# 2_-_POWER.net
KiCad netlist of a schematic drawn in Altium Designer
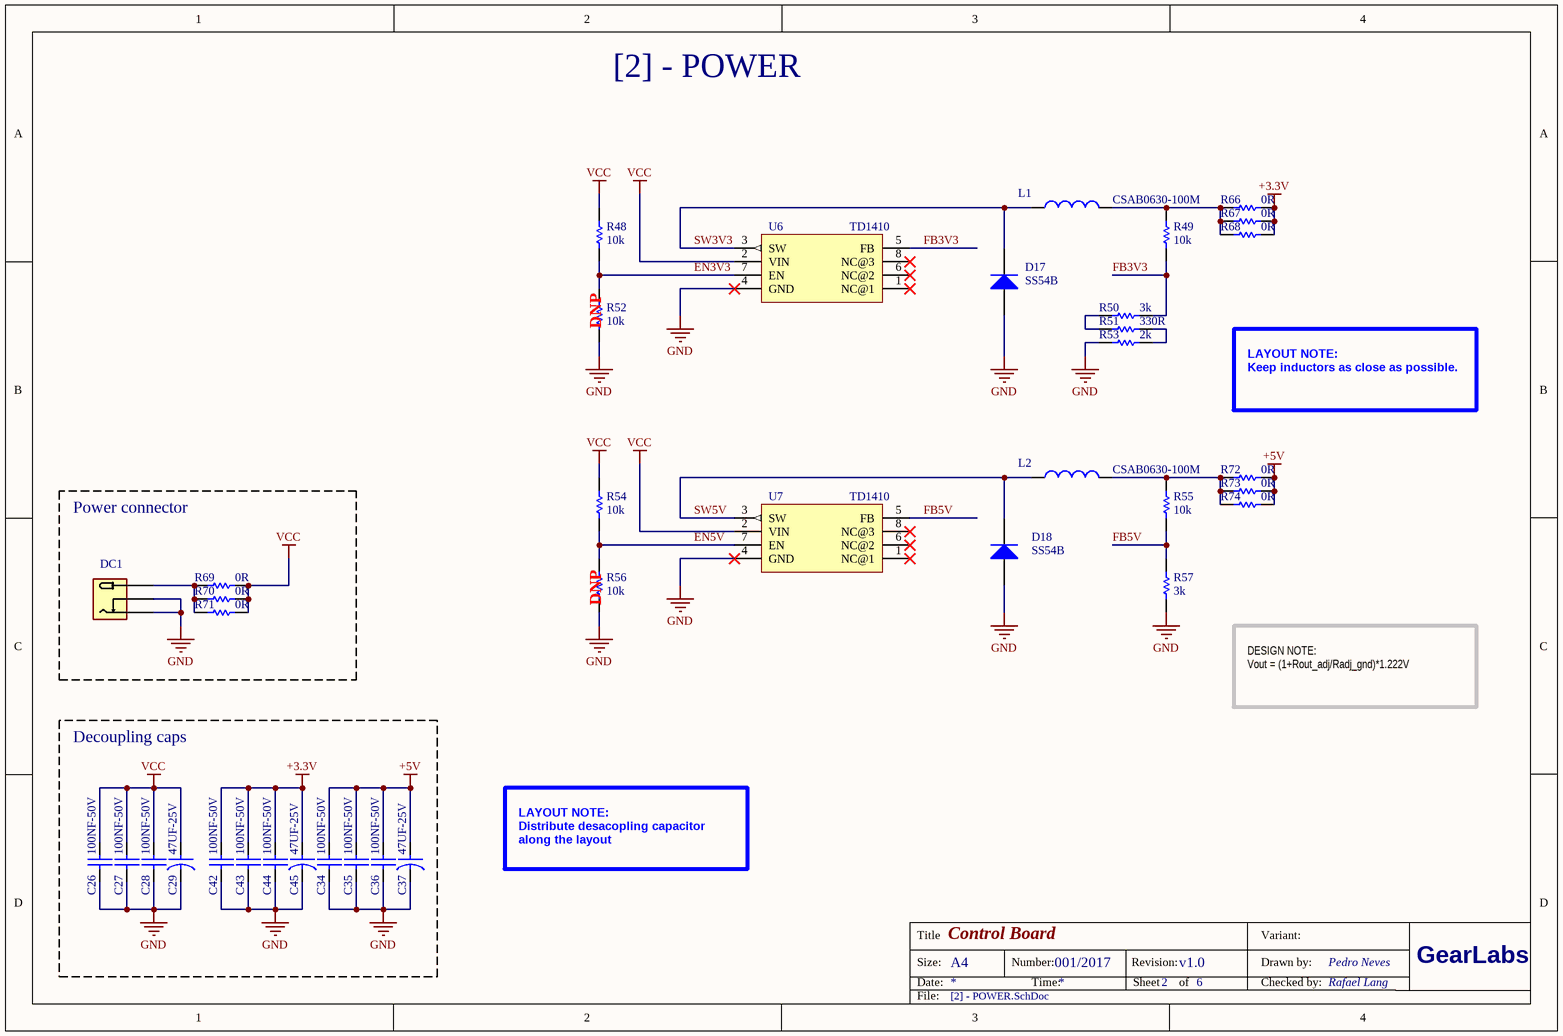
[diagram p0: [2] - POWER.SchDoc]

(export (version "E")
  (design (tool "Eeschema 10.0.6"))
  (components
    (comp (ref "C26")
      (value "100NF-50V")
      (footprint "C0603")
      (fields (field (name "MPN") "CC0603KRX7R9BB104") (field (name "Comment") "302010138"))
      (libsource (lib "Seeed-Capacitor") (part "CERAMIC-100NF-50V-10%-X7R(0603)"))
    )
    (comp (ref "C27")
      (value "100NF-50V")
      (footprint "C0603")
      (fields (field (name "MPN") "CC0603KRX7R9BB104") (field (name "Comment") "302010138"))
      (libsource (lib "Seeed-Capacitor") (part "CERAMIC-100NF-50V-10%-X7R(0603)"))
    )
    (comp (ref "C28")
      (value "100NF-50V")
      (footprint "C0603")
      (fields (field (name "MPN") "CC0603KRX7R9BB104") (field (name "Comment") "302010138"))
      (libsource (lib "Seeed-Capacitor") (part "CERAMIC-100NF-50V-10%-X7R(0603)"))
    )
    (comp (ref "C29")
      (value "47UF-25V")
      (footprint "ELECTRO-SMD-C-6MM")
      (fields (field (name "MPN") "CS1E470M-CRE54") (field (name "Comment") "302030059"))
      (libsource (lib "Seeed-Capacitor") (part "ALUMINUM-SMD-47UF-25V(D6.3-H5.3MM)"))
    )
    (comp (ref "C34")
      (value "100NF-50V")
      (footprint "C0603")
      (fields (field (name "MPN") "CC0603KRX7R9BB104") (field (name "Comment") "302010138"))
      (libsource (lib "Seeed-Capacitor") (part "CERAMIC-100NF-50V-10%-X7R(0603)"))
    )
    (comp (ref "C35")
      (value "100NF-50V")
      (footprint "C0603")
      (fields (field (name "MPN") "CC0603KRX7R9BB104") (field (name "Comment") "302010138"))
      (libsource (lib "Seeed-Capacitor") (part "CERAMIC-100NF-50V-10%-X7R(0603)"))
    )
    (comp (ref "C36")
      (value "100NF-50V")
      (footprint "C0603")
      (fields (field (name "MPN") "CC0603KRX7R9BB104") (field (name "Comment") "302010138"))
      (libsource (lib "Seeed-Capacitor") (part "CERAMIC-100NF-50V-10%-X7R(0603)"))
    )
    (comp (ref "C37")
      (value "47UF-25V")
      (footprint "ELECTRO-SMD-C-6MM")
      (fields (field (name "MPN") "CS1E470M-CRE54") (field (name "Comment") "302030059"))
      (libsource (lib "Seeed-Capacitor") (part "ALUMINUM-SMD-47UF-25V(D6.3-H5.3MM)"))
    )
    (comp (ref "C42")
      (value "100NF-50V")
      (footprint "C0603")
      (fields (field (name "MPN") "CC0603KRX7R9BB104") (field (name "Comment") "302010138"))
      (libsource (lib "Seeed-Capacitor") (part "CERAMIC-100NF-50V-10%-X7R(0603)"))
    )
    (comp (ref "C43")
      (value "100NF-50V")
      (footprint "C0603")
      (fields (field (name "MPN") "CC0603KRX7R9BB104") (field (name "Comment") "302010138"))
      (libsource (lib "Seeed-Capacitor") (part "CERAMIC-100NF-50V-10%-X7R(0603)"))
    )
    (comp (ref "C44")
      (value "100NF-50V")
      (footprint "C0603")
      (fields (field (name "MPN") "CC0603KRX7R9BB104") (field (name "Comment") "302010138"))
      (libsource (lib "Seeed-Capacitor") (part "CERAMIC-100NF-50V-10%-X7R(0603)"))
    )
    (comp (ref "C45")
      (value "47UF-25V")
      (footprint "ELECTRO-SMD-C-6MM")
      (fields (field (name "MPN") "CS1E470M-CRE54") (field (name "Comment") "302030059"))
      (libsource (lib "Seeed-Capacitor") (part "ALUMINUM-SMD-47UF-25V(D6.3-H5.3MM)"))
    )
    (comp (ref "D17")
      (value "304020021")
      (footprint "DO-214AA")
      (fields (field (name "MPN") "SS54B"))
      (libsource (lib "Seeed-Diode") (part "SMD-DIODE-SCHOTTKY-28V-5A(DO-214AA)"))
    )
    (comp (ref "D18")
      (value "304020021")
      (footprint "DO-214AA")
      (fields (field (name "MPN") "SS54B"))
      (libsource (lib "Seeed-Diode") (part "SMD-DIODE-SCHOTTKY-28V-5A(DO-214AA)"))
    )
    (comp (ref "DC1")
      (value "320120003")
      (footprint "3P-L14.2*W11.0*H9.0MM")
      (libsource (lib "Seeed-Connector") (part "JACK-DC-005'DC-005'"))
    )
    (comp (ref "L1")
      (value "303010016")
      (footprint "SMD-2P-L6.0XW6.0XH3.0MM")
      (fields (field (name "MPN") "CSAB0630-100M"))
      (libsource (lib "Seeed-Inductor") (part "SMD-INDUCTOR-10UH-20%(2P-6X6MM)'0630'"))
    )
    (comp (ref "L2")
      (value "303010016")
      (footprint "SMD-2P-L6.0XW6.0XH3.0MM")
      (fields (field (name "MPN") "CSAB0630-100M"))
      (libsource (lib "Seeed-Inductor") (part "SMD-INDUCTOR-10UH-20%(2P-6X6MM)'0630'"))
    )
    (comp (ref "R48")
      (value "10k")
      (footprint "R0603")
      (fields (field (name "MPN") "RC0603JR-0710KL") (field (name "Comment") "301010293"))
      (libsource (lib "Seeed-Resistor") (part "SMD-RES-10K-5%-1/10W(0603)"))
    )
    (comp (ref "R49")
      (value "10k")
      (footprint "R0603")
      (fields (field (name "MPN") "RC0603FR-0710KL") (field (name "Comment") "301010299"))
      (libsource (lib "Seeed-Resistor") (part "SMD-RES-10K-1%-1/10W(0603)"))
    )
    (comp (ref "R50")
      (value "3k")
      (footprint "R0603")
      (fields (field (name "MPN") "RC0603FR-073KL") (field (name "Comment") "301010170"))
      (libsource (lib "Seeed-Resistor") (part "SMD-RES-3K-1%-1/10W(0603)"))
    )
    (comp (ref "R51")
      (value "330R")
      (footprint "R0603")
      (fields (field (name "MPN") "RC0603FR-07330RL") (field (name "Comment") "301010300"))
      (libsource (lib "Seeed-Resistor") (part "SMD-RES-330R-1%-1/10W(0603)"))
    )
    (comp (ref "R52")
      (value "10k")
      (footprint "R0603")
      (fields (field (name "MPN") "RC0603JR-0710KL") (field (name "Comment") "301010293"))
      (libsource (lib "Seeed-Resistor") (part "SMD-RES-10K-5%-1/10W(0603)"))
    )
    (comp (ref "R53")
      (value "2k")
      (footprint "R0603")
      (fields (field (name "MPN") "RC0603FR-072KL") (field (name "Comment") "301010221"))
      (libsource (lib "Seeed-Resistor") (part "SMD-RES-2K-1%-1/10W(0603)"))
    )
    (comp (ref "R54")
      (value "10k")
      (footprint "R0603")
      (fields (field (name "MPN") "RC0603JR-0710KL") (field (name "Comment") "301010293"))
      (libsource (lib "Seeed-Resistor") (part "SMD-RES-10K-5%-1/10W(0603)"))
    )
    (comp (ref "R55")
      (value "10k")
      (footprint "R0603")
      (fields (field (name "MPN") "RC0603FR-0710KL") (field (name "Comment") "301010299"))
      (libsource (lib "Seeed-Resistor") (part "SMD-RES-10K-1%-1/10W(0603)"))
    )
    (comp (ref "R56")
      (value "10k")
      (footprint "R0603")
      (fields (field (name "MPN") "RC0603JR-0710KL") (field (name "Comment") "301010293"))
      (libsource (lib "Seeed-Resistor") (part "SMD-RES-10K-5%-1/10W(0603)"))
    )
    (comp (ref "R57")
      (value "3k")
      (footprint "R0603")
      (fields (field (name "MPN") "RC0603FR-073KL") (field (name "Comment") "301010170"))
      (libsource (lib "Seeed-Resistor") (part "SMD-RES-3K-1%-1/10W(0603)"))
    )
    (comp (ref "R66")
      (value "0R")
      (footprint "R0603")
      (fields (field (name "MPN") "RC0603JR-070RL") (field (name "Comment") "301010292"))
      (libsource (lib "Seeed-Resistor") (part "SMD-RES-0R-5%-1/10W(0603)"))
    )
    (comp (ref "R67")
      (value "0R")
      (footprint "R0603")
      (fields (field (name "MPN") "RC0603JR-070RL") (field (name "Comment") "301010292"))
      (libsource (lib "Seeed-Resistor") (part "SMD-RES-0R-5%-1/10W(0603)"))
    )
    (comp (ref "R68")
      (value "0R")
      (footprint "R0603")
      (fields (field (name "MPN") "RC0603JR-070RL") (field (name "Comment") "301010292"))
      (libsource (lib "Seeed-Resistor") (part "SMD-RES-0R-5%-1/10W(0603)"))
    )
    (comp (ref "R69")
      (value "0R")
      (footprint "R0603")
      (fields (field (name "MPN") "RC0603JR-070RL") (field (name "Comment") "301010292"))
      (libsource (lib "Seeed-Resistor") (part "SMD-RES-0R-5%-1/10W(0603)"))
    )
    (comp (ref "R70")
      (value "0R")
      (footprint "R0603")
      (fields (field (name "MPN") "RC0603JR-070RL") (field (name "Comment") "301010292"))
      (libsource (lib "Seeed-Resistor") (part "SMD-RES-0R-5%-1/10W(0603)"))
    )
    (comp (ref "R71")
      (value "0R")
      (footprint "R0603")
      (fields (field (name "MPN") "RC0603JR-070RL") (field (name "Comment") "301010292"))
      (libsource (lib "Seeed-Resistor") (part "SMD-RES-0R-5%-1/10W(0603)"))
    )
    (comp (ref "R72")
      (value "0R")
      (footprint "R0603")
      (fields (field (name "MPN") "RC0603JR-070RL") (field (name "Comment") "301010292"))
      (libsource (lib "Seeed-Resistor") (part "SMD-RES-0R-5%-1/10W(0603)"))
    )
    (comp (ref "R73")
      (value "0R")
      (footprint "R0603")
      (fields (field (name "MPN") "RC0603JR-070RL") (field (name "Comment") "301010292"))
      (libsource (lib "Seeed-Resistor") (part "SMD-RES-0R-5%-1/10W(0603)"))
    )
    (comp (ref "R74")
      (value "0R")
      (footprint "R0603")
      (fields (field (name "MPN") "RC0603JR-070RL") (field (name "Comment") "301010292"))
      (libsource (lib "Seeed-Resistor") (part "SMD-RES-0R-5%-1/10W(0603)"))
    )
    (comp (ref "U6")
      (value "TD1410")
      (footprint "SOIC8-1.27-5X4MM")
      (libsource (lib "Seeed-IC") (part "PMIC-TD1410(SOIC8)"))
    )
    (comp (ref "U7")
      (value "TD1410")
      (footprint "SOIC8-1.27-5X4MM")
      (libsource (lib "Seeed-IC") (part "PMIC-TD1410(SOIC8)"))
    )
  )
  (nets
    (net (code "1") (name "+3.3V") (class "Default")
      (node (ref "C42") (pin "1") (pinfunction "1_1") (pintype "passive"))
      (node (ref "C43") (pin "1") (pinfunction "1_1") (pintype "passive"))
      (node (ref "C44") (pin "1") (pinfunction "1_1") (pintype "passive"))
      (node (ref "C45") (pin "+") (pinfunction "+_+") (pintype "passive"))
      (node (ref "R66") (pin "2") (pinfunction "2_2") (pintype "passive"))
      (node (ref "R67") (pin "2") (pinfunction "2_2") (pintype "passive"))
      (node (ref "R68") (pin "2") (pinfunction "2_2") (pintype "passive"))
    )
    (net (code "2") (name "+5V") (class "Default")
      (node (ref "C34") (pin "1") (pinfunction "1_1") (pintype "passive"))
      (node (ref "C35") (pin "1") (pinfunction "1_1") (pintype "passive"))
      (node (ref "C36") (pin "1") (pinfunction "1_1") (pintype "passive"))
      (node (ref "C37") (pin "+") (pinfunction "+_+") (pintype "passive"))
      (node (ref "R72") (pin "2") (pinfunction "2_2") (pintype "passive"))
      (node (ref "R73") (pin "2") (pinfunction "2_2") (pintype "passive"))
      (node (ref "R74") (pin "2") (pinfunction "2_2") (pintype "passive"))
    )
    (net (code "3") (name "/EN3V3") (class "Default")
      (node (ref "R48") (pin "1") (pinfunction "1_1") (pintype "passive"))
      (node (ref "R52") (pin "2") (pinfunction "2_2") (pintype "passive"))
      (node (ref "U6") (pin "7") (pinfunction "EN_7") (pintype "passive"))
    )
    (net (code "4") (name "/EN5V") (class "Default")
      (node (ref "R54") (pin "1") (pinfunction "1_1") (pintype "passive"))
      (node (ref "R56") (pin "2") (pinfunction "2_2") (pintype "passive"))
      (node (ref "U7") (pin "7") (pinfunction "EN_7") (pintype "passive"))
    )
    (net (code "5") (name "/FB3V3") (class "Default")
      (node (ref "R49") (pin "1") (pinfunction "1_1") (pintype "passive"))
      (node (ref "R50") (pin "2") (pinfunction "2_2") (pintype "passive"))
      (node (ref "U6") (pin "5") (pinfunction "FB_5") (pintype "passive"))
    )
    (net (code "6") (name "/FB5V") (class "Default")
      (node (ref "R55") (pin "1") (pinfunction "1_1") (pintype "passive"))
      (node (ref "R57") (pin "2") (pinfunction "2_2") (pintype "passive"))
      (node (ref "U7") (pin "5") (pinfunction "FB_5") (pintype "passive"))
    )
    (net (code "7") (name "/SW3V3") (class "Default")
      (node (ref "D17") (pin "-") (pinfunction "-_-") (pintype "passive"))
      (node (ref "L1") (pin "1") (pinfunction "1_1") (pintype "passive"))
      (node (ref "U6") (pin "3") (pinfunction "SW_3") (pintype "output"))
    )
    (net (code "8") (name "/SW5V") (class "Default")
      (node (ref "D18") (pin "-") (pinfunction "-_-") (pintype "passive"))
      (node (ref "L2") (pin "1") (pinfunction "1_1") (pintype "passive"))
      (node (ref "U7") (pin "3") (pinfunction "SW_3") (pintype "output"))
    )
    (net (code "9") (name "GND") (class "Default")
      (node (ref "C26") (pin "2") (pinfunction "2_2") (pintype "passive"))
      (node (ref "C27") (pin "2") (pinfunction "2_2") (pintype "passive"))
      (node (ref "C28") (pin "2") (pinfunction "2_2") (pintype "passive"))
      (node (ref "C29") (pin "-") (pinfunction "-_-") (pintype "passive"))
      (node (ref "C34") (pin "2") (pinfunction "2_2") (pintype "passive"))
      (node (ref "C35") (pin "2") (pinfunction "2_2") (pintype "passive"))
      (node (ref "C36") (pin "2") (pinfunction "2_2") (pintype "passive"))
      (node (ref "C37") (pin "-") (pinfunction "-_-") (pintype "passive"))
      (node (ref "C42") (pin "2") (pinfunction "2_2") (pintype "passive"))
      (node (ref "C43") (pin "2") (pinfunction "2_2") (pintype "passive"))
      (node (ref "C44") (pin "2") (pinfunction "2_2") (pintype "passive"))
      (node (ref "C45") (pin "-") (pinfunction "-_-") (pintype "passive"))
      (node (ref "D17") (pin "+") (pinfunction "+_+") (pintype "passive"))
      (node (ref "D18") (pin "+") (pinfunction "+_+") (pintype "passive"))
      (node (ref "DC1") (pin "-1") (pinfunction "-_-1") (pintype "passive"))
      (node (ref "DC1") (pin "-2") (pinfunction "CDN_-2") (pintype "passive"))
      (node (ref "R52") (pin "1") (pinfunction "1_1") (pintype "passive"))
      (node (ref "R53") (pin "2") (pinfunction "2_2") (pintype "passive"))
      (node (ref "R56") (pin "1") (pinfunction "1_1") (pintype "passive"))
      (node (ref "R57") (pin "1") (pinfunction "1_1") (pintype "passive"))
      (node (ref "U6") (pin "4") (pinfunction "GND_4") (pintype "open_emitter"))
      (node (ref "U7") (pin "4") (pinfunction "GND_4") (pintype "open_emitter"))
    )
    (net (code "10") (name "Net-(DC1-Pad+)") (class "Default")
      (node (ref "DC1") (pin "+") (pinfunction "+_+") (pintype "passive"))
      (node (ref "R69") (pin "1") (pinfunction "1_1") (pintype "passive"))
      (node (ref "R70") (pin "1") (pinfunction "1_1") (pintype "passive"))
      (node (ref "R71") (pin "1") (pinfunction "1_1") (pintype "passive"))
    )
    (net (code "11") (name "Net-(L1-Pad2)") (class "Default")
      (node (ref "L1") (pin "2") (pinfunction "2_2") (pintype "passive"))
      (node (ref "R49") (pin "2") (pinfunction "2_2") (pintype "passive"))
      (node (ref "R66") (pin "1") (pinfunction "1_1") (pintype "passive"))
      (node (ref "R67") (pin "1") (pinfunction "1_1") (pintype "passive"))
      (node (ref "R68") (pin "1") (pinfunction "1_1") (pintype "passive"))
    )
    (net (code "12") (name "Net-(L2-Pad2)") (class "Default")
      (node (ref "L2") (pin "2") (pinfunction "2_2") (pintype "passive"))
      (node (ref "R55") (pin "2") (pinfunction "2_2") (pintype "passive"))
      (node (ref "R72") (pin "1") (pinfunction "1_1") (pintype "passive"))
      (node (ref "R73") (pin "1") (pinfunction "1_1") (pintype "passive"))
      (node (ref "R74") (pin "1") (pinfunction "1_1") (pintype "passive"))
    )
    (net (code "13") (name "Net-(R50-Pad1)") (class "Default")
      (node (ref "R50") (pin "1") (pinfunction "1_1") (pintype "passive"))
      (node (ref "R51") (pin "2") (pinfunction "2_2") (pintype "passive"))
    )
    (net (code "14") (name "Net-(R51-Pad1)") (class "Default")
      (node (ref "R51") (pin "1") (pinfunction "1_1") (pintype "passive"))
      (node (ref "R53") (pin "1") (pinfunction "1_1") (pintype "passive"))
    )
    (net (code "15") (name "VCC") (class "Default")
      (node (ref "C26") (pin "1") (pinfunction "1_1") (pintype "passive"))
      (node (ref "C27") (pin "1") (pinfunction "1_1") (pintype "passive"))
      (node (ref "C28") (pin "1") (pinfunction "1_1") (pintype "passive"))
      (node (ref "C29") (pin "+") (pinfunction "+_+") (pintype "passive"))
      (node (ref "R48") (pin "2") (pinfunction "2_2") (pintype "passive"))
      (node (ref "R54") (pin "2") (pinfunction "2_2") (pintype "passive"))
      (node (ref "R69") (pin "2") (pinfunction "2_2") (pintype "passive"))
      (node (ref "R70") (pin "2") (pinfunction "2_2") (pintype "passive"))
      (node (ref "R71") (pin "2") (pinfunction "2_2") (pintype "passive"))
      (node (ref "U6") (pin "2") (pinfunction "VIN_2") (pintype "passive"))
      (node (ref "U7") (pin "2") (pinfunction "VIN_2") (pintype "passive"))
    )
    (net (code "16") (name "unconnected-(U6-NC@1-Pad1)") (class "Default")
      (node (ref "U6") (pin "1") (pinfunction "NC@1_1") (pintype "passive+no_connect"))
    )
    (net (code "17") (name "unconnected-(U6-NC@2-Pad6)") (class "Default")
      (node (ref "U6") (pin "6") (pinfunction "NC@2_6") (pintype "passive+no_connect"))
    )
    (net (code "18") (name "unconnected-(U6-NC@3-Pad8)") (class "Default")
      (node (ref "U6") (pin "8") (pinfunction "NC@3_8") (pintype "passive+no_connect"))
    )
    (net (code "19") (name "unconnected-(U7-NC@1-Pad1)") (class "Default")
      (node (ref "U7") (pin "1") (pinfunction "NC@1_1") (pintype "passive+no_connect"))
    )
    (net (code "20") (name "unconnected-(U7-NC@2-Pad6)") (class "Default")
      (node (ref "U7") (pin "6") (pinfunction "NC@2_6") (pintype "passive+no_connect"))
    )
    (net (code "21") (name "unconnected-(U7-NC@3-Pad8)") (class "Default")
      (node (ref "U7") (pin "8") (pinfunction "NC@3_8") (pintype "passive+no_connect"))
    )
  )
)
